# F303K8T6.net
KiCad netlist of a schematic drawn in EAGLE
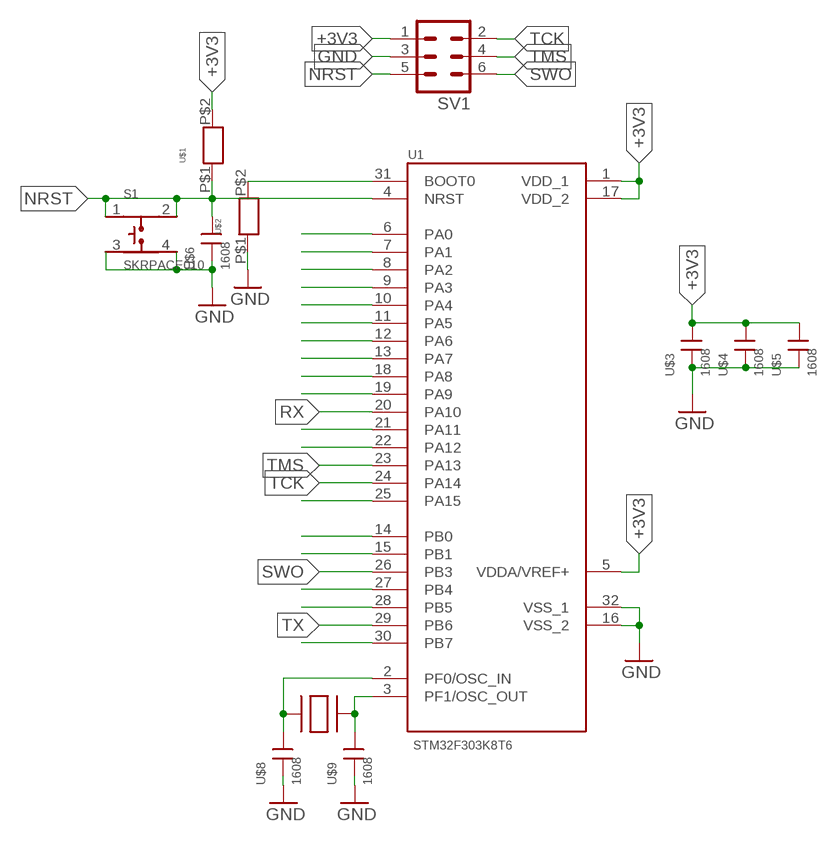
[diagram p0: schematic, sheet 1]

(export (version "E")
  (design (tool "Eeschema 10.0.6"))
  (components
    (comp (ref "S1")
      (value "SKRPACE010")
      (footprint "eagle-import:SW_SKRPACE010")
      (fields (field (name "MF") "ALPS"))
      (libsource (lib "eagle-import") (part "SKRPACE010"))
    )
    (comp (ref "SV1")
      (value "ML6")
      (footprint "eagle-import:ML6")
      (libsource (lib "eagle-import") (part "ML6"))
    )
    (comp (ref "U$1") (value "R") (footprint "eagle-import:1608") (libsource (lib "eagle-import") (part "R")))
    (comp (ref "U$2") (value "R") (footprint "eagle-import:1608") (libsource (lib "eagle-import") (part "R")))
    (comp (ref "U$3")
      (value "1608")
      (footprint "eagle-import:CON")
      (libsource (lib "eagle-import") (part "1608"))
    )
    (comp (ref "U$4")
      (value "1608")
      (footprint "eagle-import:CON")
      (libsource (lib "eagle-import") (part "1608"))
    )
    (comp (ref "U$5")
      (value "1608")
      (footprint "eagle-import:CON")
      (libsource (lib "eagle-import") (part "1608"))
    )
    (comp (ref "U$6")
      (value "1608")
      (footprint "eagle-import:CON")
      (libsource (lib "eagle-import") (part "1608"))
    )
    (comp (ref "U$7")
      (value "SUISYOU")
      (footprint "eagle-import:水晶")
      (libsource (lib "eagle-import") (part "SUISYOU"))
    )
    (comp (ref "U$8")
      (value "1608")
      (footprint "eagle-import:CON")
      (libsource (lib "eagle-import") (part "1608"))
    )
    (comp (ref "U$9")
      (value "1608")
      (footprint "eagle-import:CON")
      (libsource (lib "eagle-import") (part "1608"))
    )
    (comp (ref "U1")
      (value "STM32F303K8T6")
      (footprint "eagle-import:QFP80P900X900X160-32N")
      (fields (field (name "MF") "STMicroelectronics"))
      (libsource (lib "eagle-import") (part "STM32F303K8T6"))
    )
  )
  (nets
    (net (code "1") (name "+3V3") (class "Default")
      (node (ref "SV1") (pin "1") (pinfunction "1_1") (pintype "passive"))
      (node (ref "U$1") (pin "P$2") (pinfunction "P$2_P$2") (pintype "bidirectional"))
      (node (ref "U$3") (pin "P$1") (pinfunction "1_P$1") (pintype "bidirectional"))
      (node (ref "U$4") (pin "P$1") (pinfunction "1_P$1") (pintype "bidirectional"))
      (node (ref "U$5") (pin "P$1") (pinfunction "1_P$1") (pintype "bidirectional"))
      (node (ref "U1") (pin "1") (pinfunction "VDD_1_1") (pintype "power_in"))
      (node (ref "U1") (pin "17") (pinfunction "VDD_2_17") (pintype "power_in"))
      (node (ref "U1") (pin "5") (pinfunction "VDDA/VREF+_5") (pintype "power_in"))
    )
    (net (code "2") (name "GND") (class "Default")
      (node (ref "S1") (pin "3") (pinfunction "3_3") (pintype "bidirectional"))
      (node (ref "S1") (pin "4") (pinfunction "4_4") (pintype "bidirectional"))
      (node (ref "SV1") (pin "3") (pinfunction "3_3") (pintype "passive"))
      (node (ref "U$2") (pin "P$1") (pinfunction "P$1_P$1") (pintype "bidirectional"))
      (node (ref "U$3") (pin "P$2") (pinfunction "2_P$2") (pintype "bidirectional"))
      (node (ref "U$4") (pin "P$2") (pinfunction "2_P$2") (pintype "bidirectional"))
      (node (ref "U$5") (pin "P$2") (pinfunction "2_P$2") (pintype "bidirectional"))
      (node (ref "U$6") (pin "P$2") (pinfunction "2_P$2") (pintype "bidirectional"))
      (node (ref "U$8") (pin "P$2") (pinfunction "2_P$2") (pintype "bidirectional"))
      (node (ref "U$9") (pin "P$2") (pinfunction "2_P$2") (pintype "bidirectional"))
      (node (ref "U1") (pin "16") (pinfunction "VSS_2_16") (pintype "power_in"))
      (node (ref "U1") (pin "32") (pinfunction "VSS_1_32") (pintype "power_in"))
    )
    (net (code "3") (name "NRST") (class "Default")
      (node (ref "S1") (pin "1") (pinfunction "1_1") (pintype "bidirectional"))
      (node (ref "S1") (pin "2") (pinfunction "2_2") (pintype "bidirectional"))
      (node (ref "SV1") (pin "5") (pinfunction "5_5") (pintype "passive"))
      (node (ref "U$1") (pin "P$1") (pinfunction "P$1_P$1") (pintype "bidirectional"))
      (node (ref "U$6") (pin "P$1") (pinfunction "1_P$1") (pintype "bidirectional"))
      (node (ref "U1") (pin "4") (pinfunction "NRST_4") (pintype "bidirectional"))
    )
    (net (code "4") (name "Net-(U$8-1)") (class "Default")
      (node (ref "U$7") (pin "P$1") (pinfunction "P$1_P$1") (pintype "bidirectional"))
      (node (ref "U$8") (pin "P$1") (pinfunction "1_P$1") (pintype "bidirectional"))
      (node (ref "U1") (pin "2") (pinfunction "PF0/OSC_IN_2") (pintype "bidirectional"))
    )
    (net (code "5") (name "Net-(U$9-1)") (class "Default")
      (node (ref "U$7") (pin "P$2") (pinfunction "P$2_P$2") (pintype "bidirectional"))
      (node (ref "U$9") (pin "P$1") (pinfunction "1_P$1") (pintype "bidirectional"))
      (node (ref "U1") (pin "3") (pinfunction "PF1/OSC_OUT_3") (pintype "bidirectional"))
    )
    (net (code "6") (name "Net-(U1-BOOT0)") (class "Default")
      (node (ref "U$2") (pin "P$2") (pinfunction "P$2_P$2") (pintype "bidirectional"))
      (node (ref "U1") (pin "31") (pinfunction "BOOT0_31") (pintype "input"))
    )
    (net (code "7") (name "RX") (class "Default")
      (node (ref "U1") (pin "20") (pinfunction "PA10_20") (pintype "bidirectional"))
    )
    (net (code "8") (name "SWO") (class "Default")
      (node (ref "SV1") (pin "6") (pinfunction "6_6") (pintype "passive"))
      (node (ref "U1") (pin "26") (pinfunction "PB3_26") (pintype "bidirectional"))
    )
    (net (code "9") (name "TCK") (class "Default")
      (node (ref "SV1") (pin "2") (pinfunction "2_2") (pintype "passive"))
      (node (ref "U1") (pin "24") (pinfunction "PA14_24") (pintype "bidirectional"))
    )
    (net (code "10") (name "TMS") (class "Default")
      (node (ref "SV1") (pin "4") (pinfunction "4_4") (pintype "passive"))
      (node (ref "U1") (pin "23") (pinfunction "PA13_23") (pintype "bidirectional"))
    )
    (net (code "11") (name "TX") (class "Default")
      (node (ref "U1") (pin "29") (pinfunction "PB6_29") (pintype "bidirectional"))
    )
    (net (code "12") (name "unconnected-(U1-PA0-Pad6)") (class "Default")
      (node (ref "U1") (pin "6") (pinfunction "PA0_6") (pintype "bidirectional"))
    )
    (net (code "13") (name "unconnected-(U1-PA1-Pad7)") (class "Default")
      (node (ref "U1") (pin "7") (pinfunction "PA1_7") (pintype "bidirectional"))
    )
    (net (code "14") (name "unconnected-(U1-PA2-Pad8)") (class "Default")
      (node (ref "U1") (pin "8") (pinfunction "PA2_8") (pintype "bidirectional"))
    )
    (net (code "15") (name "unconnected-(U1-PA3-Pad9)") (class "Default")
      (node (ref "U1") (pin "9") (pinfunction "PA3_9") (pintype "bidirectional"))
    )
    (net (code "16") (name "unconnected-(U1-PA4-Pad10)") (class "Default")
      (node (ref "U1") (pin "10") (pinfunction "PA4_10") (pintype "bidirectional"))
    )
    (net (code "17") (name "unconnected-(U1-PA5-Pad11)") (class "Default")
      (node (ref "U1") (pin "11") (pinfunction "PA5_11") (pintype "bidirectional"))
    )
    (net (code "18") (name "unconnected-(U1-PA6-Pad12)") (class "Default")
      (node (ref "U1") (pin "12") (pinfunction "PA6_12") (pintype "bidirectional"))
    )
    (net (code "19") (name "unconnected-(U1-PA7-Pad13)") (class "Default")
      (node (ref "U1") (pin "13") (pinfunction "PA7_13") (pintype "bidirectional"))
    )
    (net (code "20") (name "unconnected-(U1-PA8-Pad18)") (class "Default")
      (node (ref "U1") (pin "18") (pinfunction "PA8_18") (pintype "bidirectional"))
    )
    (net (code "21") (name "unconnected-(U1-PA9-Pad19)") (class "Default")
      (node (ref "U1") (pin "19") (pinfunction "PA9_19") (pintype "bidirectional"))
    )
    (net (code "22") (name "unconnected-(U1-PA11-Pad21)") (class "Default")
      (node (ref "U1") (pin "21") (pinfunction "PA11_21") (pintype "bidirectional"))
    )
    (net (code "23") (name "unconnected-(U1-PA12-Pad22)") (class "Default")
      (node (ref "U1") (pin "22") (pinfunction "PA12_22") (pintype "bidirectional"))
    )
    (net (code "24") (name "unconnected-(U1-PA15-Pad25)") (class "Default")
      (node (ref "U1") (pin "25") (pinfunction "PA15_25") (pintype "bidirectional"))
    )
    (net (code "25") (name "unconnected-(U1-PB0-Pad14)") (class "Default")
      (node (ref "U1") (pin "14") (pinfunction "PB0_14") (pintype "bidirectional"))
    )
    (net (code "26") (name "unconnected-(U1-PB1-Pad15)") (class "Default")
      (node (ref "U1") (pin "15") (pinfunction "PB1_15") (pintype "bidirectional"))
    )
    (net (code "27") (name "unconnected-(U1-PB4-Pad27)") (class "Default")
      (node (ref "U1") (pin "27") (pinfunction "PB4_27") (pintype "bidirectional"))
    )
    (net (code "28") (name "unconnected-(U1-PB5-Pad28)") (class "Default")
      (node (ref "U1") (pin "28") (pinfunction "PB5_28") (pintype "bidirectional"))
    )
    (net (code "29") (name "unconnected-(U1-PB7-Pad30)") (class "Default")
      (node (ref "U1") (pin "30") (pinfunction "PB7_30") (pintype "bidirectional"))
    )
  )
)
